# CompletePCBV3.net
KiCad netlist of a schematic drawn in EAGLE
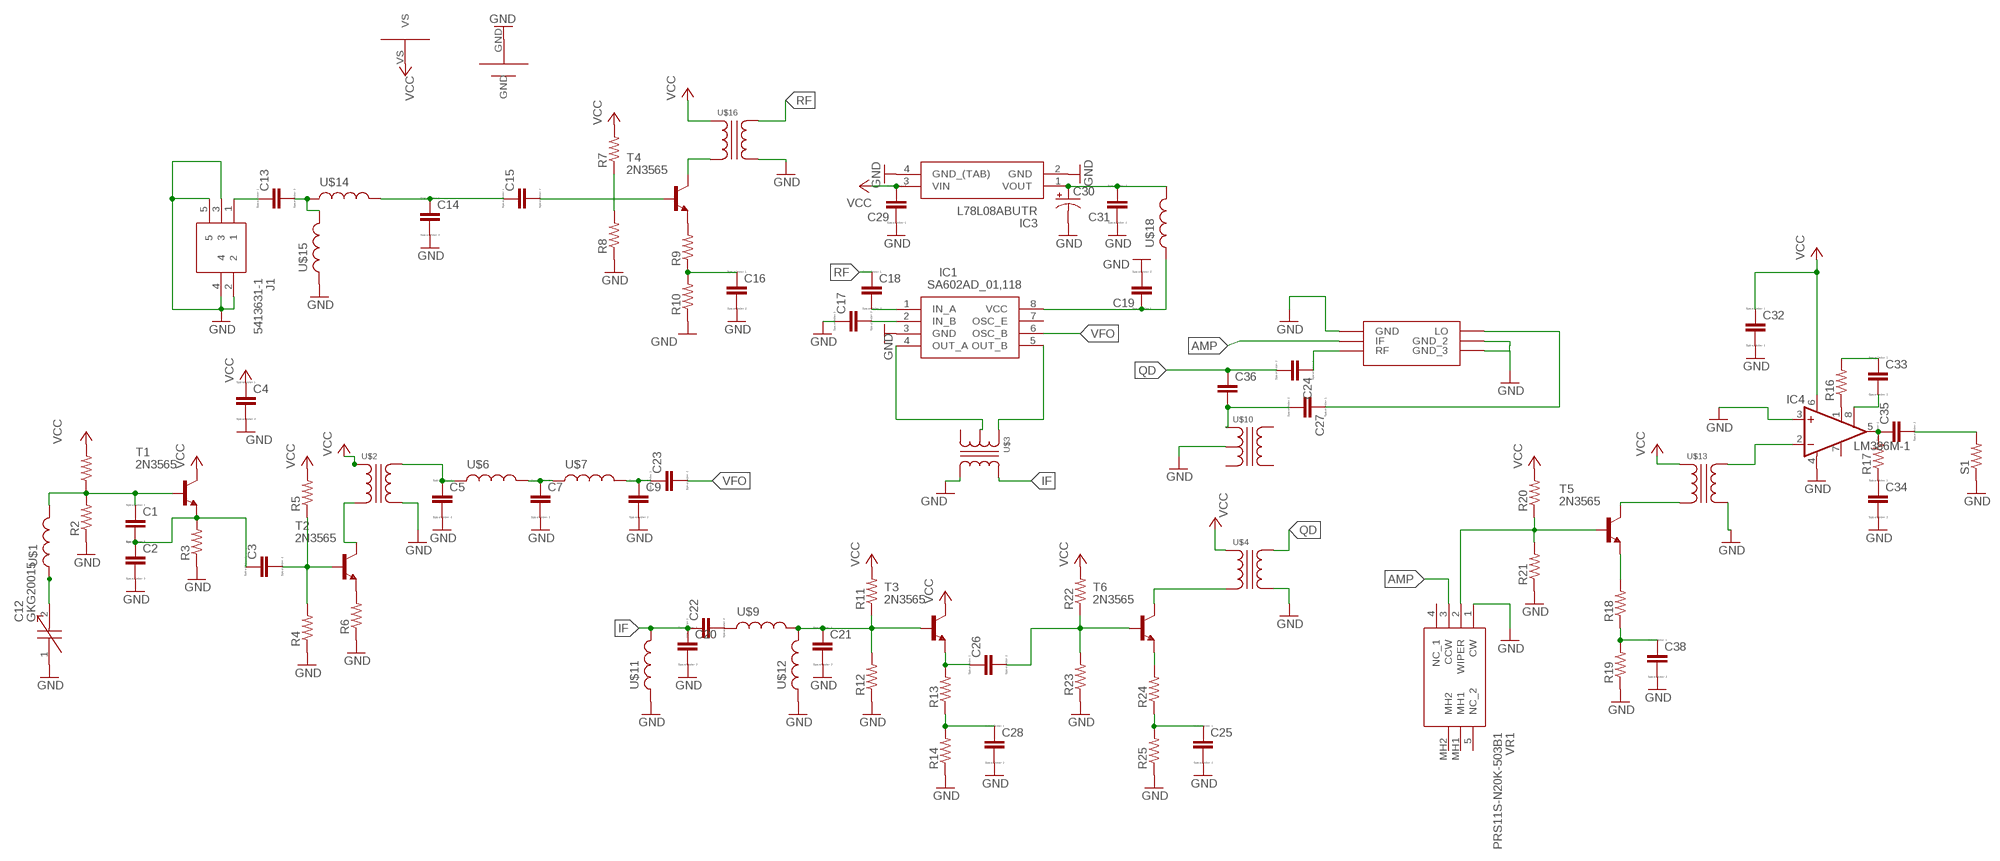
[diagram p0: schematic, sheet 1]

(export (version "E")
  (design (tool "Eeschema 10.0.6"))
  (components
    (comp (ref "C1") (value "C") (footprint "eagle-import:C0805") (libsource (lib "eagle-import") (part "C")))
    (comp (ref "C2") (value "C") (footprint "eagle-import:C0805") (libsource (lib "eagle-import") (part "C")))
    (comp (ref "C3") (value "C") (footprint "eagle-import:C0805") (libsource (lib "eagle-import") (part "C")))
    (comp (ref "C4") (value "C") (footprint "eagle-import:C0805") (libsource (lib "eagle-import") (part "C")))
    (comp (ref "C5") (value "C") (footprint "eagle-import:C0805") (libsource (lib "eagle-import") (part "C")))
    (comp (ref "C7") (value "C") (footprint "eagle-import:C0805") (libsource (lib "eagle-import") (part "C")))
    (comp (ref "C9") (value "C") (footprint "eagle-import:C0805") (libsource (lib "eagle-import") (part "C")))
    (comp (ref "C12")
      (value "GKG20015")
      (footprint "eagle-import:GKG20015")
      (fields (field (name "MOUSER_PART_NUMBER") "659-GKG20015"))
      (libsource (lib "eagle-import") (part "GKG20015"))
    )
    (comp (ref "C13")
      (value "C")
      (footprint "eagle-import:C0805")
      (libsource (lib "eagle-import") (part "C"))
    )
    (comp (ref "C14")
      (value "C")
      (footprint "eagle-import:C0805")
      (libsource (lib "eagle-import") (part "C"))
    )
    (comp (ref "C15")
      (value "C")
      (footprint "eagle-import:C0805")
      (libsource (lib "eagle-import") (part "C"))
    )
    (comp (ref "C16")
      (value "C")
      (footprint "eagle-import:C0805")
      (libsource (lib "eagle-import") (part "C"))
    )
    (comp (ref "C17")
      (value "C")
      (footprint "eagle-import:C0805")
      (libsource (lib "eagle-import") (part "C"))
    )
    (comp (ref "C18")
      (value "C")
      (footprint "eagle-import:C0805")
      (libsource (lib "eagle-import") (part "C"))
    )
    (comp (ref "C19")
      (value "C")
      (footprint "eagle-import:C0805")
      (libsource (lib "eagle-import") (part "C"))
    )
    (comp (ref "C20")
      (value "C")
      (footprint "eagle-import:C0805")
      (libsource (lib "eagle-import") (part "C"))
    )
    (comp (ref "C21")
      (value "C")
      (footprint "eagle-import:C0805")
      (libsource (lib "eagle-import") (part "C"))
    )
    (comp (ref "C22")
      (value "C")
      (footprint "eagle-import:C0805")
      (libsource (lib "eagle-import") (part "C"))
    )
    (comp (ref "C23")
      (value "C")
      (footprint "eagle-import:C0805")
      (libsource (lib "eagle-import") (part "C"))
    )
    (comp (ref "C24")
      (value "C")
      (footprint "eagle-import:C0805")
      (libsource (lib "eagle-import") (part "C"))
    )
    (comp (ref "C25")
      (value "C")
      (footprint "eagle-import:C0805")
      (libsource (lib "eagle-import") (part "C"))
    )
    (comp (ref "C26")
      (value "C")
      (footprint "eagle-import:C0805")
      (libsource (lib "eagle-import") (part "C"))
    )
    (comp (ref "C27")
      (value "C")
      (footprint "eagle-import:C0805")
      (libsource (lib "eagle-import") (part "C"))
    )
    (comp (ref "C28")
      (value "C")
      (footprint "eagle-import:C0805")
      (libsource (lib "eagle-import") (part "C"))
    )
    (comp (ref "C29")
      (value "C")
      (footprint "eagle-import:C0805")
      (libsource (lib "eagle-import") (part "C"))
    )
    (comp (ref "C30")
      (value "CPOL-US175TMP-0808")
      (footprint "eagle-import:175TMP-0808")
      (libsource (lib "eagle-import") (part "CPOL-US175TMP-0808"))
    )
    (comp (ref "C31")
      (value "C")
      (footprint "eagle-import:C0805")
      (libsource (lib "eagle-import") (part "C"))
    )
    (comp (ref "C32")
      (value "C")
      (footprint "eagle-import:C0805")
      (libsource (lib "eagle-import") (part "C"))
    )
    (comp (ref "C33")
      (value "C")
      (footprint "eagle-import:C0805")
      (libsource (lib "eagle-import") (part "C"))
    )
    (comp (ref "C34")
      (value "C")
      (footprint "eagle-import:C0805")
      (libsource (lib "eagle-import") (part "C"))
    )
    (comp (ref "C35")
      (value "C")
      (footprint "eagle-import:C0805")
      (libsource (lib "eagle-import") (part "C"))
    )
    (comp (ref "C36")
      (value "C-EUC0603")
      (footprint "eagle-import:C0603")
      (libsource (lib "eagle-import") (part "C-EUC0603"))
    )
    (comp (ref "C38")
      (value "C")
      (footprint "eagle-import:C0805")
      (libsource (lib "eagle-import") (part "C"))
    )
    (comp (ref "IC1")
      (value "SA602AD_01,118")
      (footprint "eagle-import:SOIC127P600X175-8N")
      (fields
        (field (name "MANUFACTURER_PART_NUMBER") "SA602AD/01,118")
        (field (name "MOUSER_PART_NUMBER") "771-SA602AD/01-T")
      )
      (libsource (lib "eagle-import") (part "SA602AD_01,118"))
    )
    (comp (ref "IC3")
      (value "L78L08ABUTR")
      (footprint "eagle-import:ST-SOT-89")
      (fields (field (name "MOUSER_PART_NUMBER") "511-L78L08ABU"))
      (libsource (lib "eagle-import") (part "L78L08ABUTR"))
    )
    (comp (ref "IC4")
      (value "LM386M-1")
      (footprint "eagle-import:SO08")
      (libsource (lib "eagle-import") (part "LM386?-M1"))
    )
    (comp (ref "J1")
      (value "5413631-1")
      (footprint "eagle-import:54136311")
      (fields (field (name "MOUSER_PART_NUMBER") "571-5413631-1"))
      (libsource (lib "eagle-import") (part "5413631-1"))
    )
    (comp (ref "R1")
      (value "R-US_R0805")
      (footprint "eagle-import:R0805")
      (libsource (lib "eagle-import") (part "resistor_348_R-US_R0805"))
    )
    (comp (ref "R2")
      (value "R-US_R0805")
      (footprint "eagle-import:R0805")
      (libsource (lib "eagle-import") (part "resistor_348_R-US_R0805"))
    )
    (comp (ref "R3")
      (value "R-US_R0805")
      (footprint "eagle-import:R0805")
      (libsource (lib "eagle-import") (part "resistor_348_R-US_R0805"))
    )
    (comp (ref "R4")
      (value "R-US_R0805")
      (footprint "eagle-import:R0805")
      (libsource (lib "eagle-import") (part "resistor_348_R-US_R0805"))
    )
    (comp (ref "R5")
      (value "R-US_R0805")
      (footprint "eagle-import:R0805")
      (libsource (lib "eagle-import") (part "resistor_348_R-US_R0805"))
    )
    (comp (ref "R6")
      (value "R-US_R0805")
      (footprint "eagle-import:R0805")
      (libsource (lib "eagle-import") (part "resistor_348_R-US_R0805"))
    )
    (comp (ref "R7")
      (value "R-US_R0805")
      (footprint "eagle-import:R0805")
      (libsource (lib "eagle-import") (part "resistor_348_R-US_R0805"))
    )
    (comp (ref "R8")
      (value "R-US_R0805")
      (footprint "eagle-import:R0805")
      (libsource (lib "eagle-import") (part "resistor_348_R-US_R0805"))
    )
    (comp (ref "R9")
      (value "R-US_R0805")
      (footprint "eagle-import:R0805")
      (libsource (lib "eagle-import") (part "resistor_348_R-US_R0805"))
    )
    (comp (ref "R10")
      (value "R-US_R0805")
      (footprint "eagle-import:R0805")
      (libsource (lib "eagle-import") (part "resistor_348_R-US_R0805"))
    )
    (comp (ref "R11")
      (value "R-US_R0805")
      (footprint "eagle-import:R0805")
      (libsource (lib "eagle-import") (part "resistor_348_R-US_R0805"))
    )
    (comp (ref "R12")
      (value "R-US_R0805")
      (footprint "eagle-import:R0805")
      (libsource (lib "eagle-import") (part "resistor_348_R-US_R0805"))
    )
    (comp (ref "R13")
      (value "R-US_R0805")
      (footprint "eagle-import:R0805")
      (libsource (lib "eagle-import") (part "resistor_348_R-US_R0805"))
    )
    (comp (ref "R14")
      (value "R-US_R0805")
      (footprint "eagle-import:R0805")
      (libsource (lib "eagle-import") (part "resistor_348_R-US_R0805"))
    )
    (comp (ref "R16")
      (value "R-US_R0805")
      (footprint "eagle-import:R0805")
      (libsource (lib "eagle-import") (part "resistor_348_R-US_R0805"))
    )
    (comp (ref "R17")
      (value "R-US_R0805")
      (footprint "eagle-import:R0805")
      (libsource (lib "eagle-import") (part "resistor_348_R-US_R0805"))
    )
    (comp (ref "R18")
      (value "R-US_R0805")
      (footprint "eagle-import:R0805")
      (libsource (lib "eagle-import") (part "resistor_348_R-US_R0805"))
    )
    (comp (ref "R19")
      (value "R-US_R0805")
      (footprint "eagle-import:R0805")
      (libsource (lib "eagle-import") (part "resistor_348_R-US_R0805"))
    )
    (comp (ref "R20")
      (value "R-US_R0805")
      (footprint "eagle-import:R0805")
      (libsource (lib "eagle-import") (part "resistor_348_R-US_R0805"))
    )
    (comp (ref "R21")
      (value "R-US_R0805")
      (footprint "eagle-import:R0805")
      (libsource (lib "eagle-import") (part "resistor_348_R-US_R0805"))
    )
    (comp (ref "R22")
      (value "R-US_R0805")
      (footprint "eagle-import:R0805")
      (libsource (lib "eagle-import") (part "resistor_348_R-US_R0805"))
    )
    (comp (ref "R23")
      (value "R-US_R0805")
      (footprint "eagle-import:R0805")
      (libsource (lib "eagle-import") (part "resistor_348_R-US_R0805"))
    )
    (comp (ref "R24")
      (value "R-US_R0805")
      (footprint "eagle-import:R0805")
      (libsource (lib "eagle-import") (part "resistor_348_R-US_R0805"))
    )
    (comp (ref "R25")
      (value "R-US_R0805")
      (footprint "eagle-import:R0805")
      (libsource (lib "eagle-import") (part "resistor_348_R-US_R0805"))
    )
    (comp (ref "S1")
      (value "R-US_0207/5V")
      (footprint "eagle-import:0207_5V")
      (libsource (lib "eagle-import") (part "R-US_0207/5V"))
    )
    (comp (ref "T1")
      (value "2N3565")
      (footprint "eagle-import:TO92")
      (libsource (lib "eagle-import") (part "2N3565"))
    )
    (comp (ref "T2")
      (value "2N3565")
      (footprint "eagle-import:TO92")
      (libsource (lib "eagle-import") (part "2N3565"))
    )
    (comp (ref "T3")
      (value "2N3565")
      (footprint "eagle-import:TO92")
      (libsource (lib "eagle-import") (part "2N3565"))
    )
    (comp (ref "T4")
      (value "2N3565")
      (footprint "eagle-import:TO92")
      (libsource (lib "eagle-import") (part "2N3565"))
    )
    (comp (ref "T5")
      (value "2N3565")
      (footprint "eagle-import:TO92")
      (libsource (lib "eagle-import") (part "2N3565"))
    )
    (comp (ref "T6")
      (value "2N3565")
      (footprint "eagle-import:TO92")
      (libsource (lib "eagle-import") (part "2N3565"))
    )
    (comp (ref "U$1")
      (value "WOUNDINDUCTOR")
      (footprint "eagle-import:WOUNDINDUCTOR")
      (libsource (lib "eagle-import") (part "WOUNDINDUCTOR"))
    )
    (comp (ref "U$2")
      (value "RFTRANSFORMER")
      (footprint "eagle-import:RFTRABSFORMER")
      (libsource (lib "eagle-import") (part "RFTRANSFORMER"))
    )
    (comp (ref "U$3")
      (value "42IF123")
      (footprint "eagle-import:42IF123")
      (libsource (lib "eagle-import") (part "42IF123"))
    )
    (comp (ref "U$4")
      (value "RFTRANSFORMER")
      (footprint "eagle-import:RFTRABSFORMER")
      (libsource (lib "eagle-import") (part "RFTRANSFORMER"))
    )
    (comp (ref "U$5")
      (value "ALLIGATORCLIPS")
      (footprint "eagle-import:ALLIGATORCONNECTOR")
      (libsource (lib "eagle-import") (part "ALLIGATORCLIPS"))
    )
    (comp (ref "U$6")
      (value "WOUNDINDUCTOR")
      (footprint "eagle-import:WOUNDINDUCTOR")
      (libsource (lib "eagle-import") (part "WOUNDINDUCTOR"))
    )
    (comp (ref "U$7")
      (value "WOUNDINDUCTOR")
      (footprint "eagle-import:WOUNDINDUCTOR")
      (libsource (lib "eagle-import") (part "WOUNDINDUCTOR"))
    )
    (comp (ref "U$9")
      (value "WOUNDINDUCTOR")
      (footprint "eagle-import:WOUNDINDUCTOR")
      (libsource (lib "eagle-import") (part "WOUNDINDUCTOR"))
    )
    (comp (ref "U$10")
      (value "42IF123")
      (footprint "eagle-import:42IF123")
      (libsource (lib "eagle-import") (part "42IF123"))
    )
    (comp (ref "U$11")
      (value "WOUNDINDUCTOR")
      (footprint "eagle-import:WOUNDINDUCTOR")
      (libsource (lib "eagle-import") (part "WOUNDINDUCTOR"))
    )
    (comp (ref "U$12")
      (value "WOUNDINDUCTOR")
      (footprint "eagle-import:WOUNDINDUCTOR")
      (libsource (lib "eagle-import") (part "WOUNDINDUCTOR"))
    )
    (comp (ref "U$13")
      (value "RFTRANSFORMER")
      (footprint "eagle-import:RFTRABSFORMER")
      (libsource (lib "eagle-import") (part "RFTRANSFORMER"))
    )
    (comp (ref "U$14")
      (value "WOUNDINDUCTOR")
      (footprint "eagle-import:WOUNDINDUCTOR")
      (libsource (lib "eagle-import") (part "WOUNDINDUCTOR"))
    )
    (comp (ref "U$15")
      (value "WOUNDINDUCTOR")
      (footprint "eagle-import:WOUNDINDUCTOR")
      (libsource (lib "eagle-import") (part "WOUNDINDUCTOR"))
    )
    (comp (ref "U$16")
      (value "RFTRANSFORMER")
      (footprint "eagle-import:RFTRABSFORMER")
      (libsource (lib "eagle-import") (part "RFTRANSFORMER"))
    )
    (comp (ref "U$17")
      (value "ADE-1")
      (footprint "eagle-import:ADE-1")
      (libsource (lib "eagle-import") (part "ADE-1"))
    )
    (comp (ref "U$18")
      (value "WOUNDINDUCTOR")
      (footprint "eagle-import:WOUNDINDUCTOR")
      (libsource (lib "eagle-import") (part "WOUNDINDUCTOR"))
    )
    (comp (ref "VR1")
      (value "PRS11S-N20K-503B1")
      (footprint "eagle-import:PRS11SN20K503B1")
      (fields (field (name "MOUSER_PART_NUMBER") "652-PRS11SN20K503B1"))
      (libsource (lib "eagle-import") (part "PRS11S-N20K-503B1"))
    )
  )
  (nets
    (net (code "1") (name "AMP") (class "Default")
      (node (ref "U$17") (pin "IF") (pinfunction "IF_IF") (pintype "bidirectional"))
      (node (ref "VR1") (pin "3") (pinfunction "CCW_3") (pintype "bidirectional"))
    )
    (net (code "2") (name "GND") (class "Default")
      (node (ref "C12") (pin "1") (pinfunction "1_1") (pintype "bidirectional"))
      (node (ref "C14") (pin "2") (pinfunction "2_2") (pintype "passive"))
      (node (ref "C16") (pin "2") (pinfunction "2_2") (pintype "passive"))
      (node (ref "C17") (pin "1") (pinfunction "1_1") (pintype "passive"))
      (node (ref "C19") (pin "2") (pinfunction "2_2") (pintype "passive"))
      (node (ref "C2") (pin "2") (pinfunction "2_2") (pintype "passive"))
      (node (ref "C20") (pin "2") (pinfunction "2_2") (pintype "passive"))
      (node (ref "C21") (pin "2") (pinfunction "2_2") (pintype "passive"))
      (node (ref "C25") (pin "2") (pinfunction "2_2") (pintype "passive"))
      (node (ref "C28") (pin "2") (pinfunction "2_2") (pintype "passive"))
      (node (ref "C29") (pin "1") (pinfunction "1_1") (pintype "passive"))
      (node (ref "C30") (pin "-") (pinfunction "-_-") (pintype "passive"))
      (node (ref "C31") (pin "1") (pinfunction "1_1") (pintype "passive"))
      (node (ref "C32") (pin "2") (pinfunction "2_2") (pintype "passive"))
      (node (ref "C34") (pin "2") (pinfunction "2_2") (pintype "passive"))
      (node (ref "C38") (pin "2") (pinfunction "2_2") (pintype "passive"))
      (node (ref "C4") (pin "2") (pinfunction "2_2") (pintype "passive"))
      (node (ref "C5") (pin "2") (pinfunction "2_2") (pintype "passive"))
      (node (ref "C7") (pin "2") (pinfunction "2_2") (pintype "passive"))
      (node (ref "C9") (pin "2") (pinfunction "2_2") (pintype "passive"))
      (node (ref "IC1") (pin "3") (pinfunction "GND_3") (pintype "power_in"))
      (node (ref "IC3") (pin "2") (pinfunction "GND_2") (pintype "power_in"))
      (node (ref "IC3") (pin "4") (pinfunction "GND_(TAB)_4") (pintype "power_in"))
      (node (ref "IC4") (pin "3") (pinfunction "+IN_3") (pintype "input"))
      (node (ref "IC4") (pin "4") (pinfunction "GND_4") (pintype "power_in"))
      (node (ref "J1") (pin "2") (pinfunction "2_2") (pintype "bidirectional"))
      (node (ref "J1") (pin "3") (pinfunction "3_3") (pintype "bidirectional"))
      (node (ref "J1") (pin "4") (pinfunction "4_4") (pintype "bidirectional"))
      (node (ref "J1") (pin "5") (pinfunction "5_5") (pintype "bidirectional"))
      (node (ref "R10") (pin "1") (pinfunction "1_1") (pintype "passive"))
      (node (ref "R12") (pin "1") (pinfunction "1_1") (pintype "passive"))
      (node (ref "R14") (pin "1") (pinfunction "1_1") (pintype "passive"))
      (node (ref "R19") (pin "1") (pinfunction "1_1") (pintype "passive"))
      (node (ref "R2") (pin "1") (pinfunction "1_1") (pintype "passive"))
      (node (ref "R21") (pin "1") (pinfunction "1_1") (pintype "passive"))
      (node (ref "R23") (pin "1") (pinfunction "1_1") (pintype "passive"))
      (node (ref "R25") (pin "1") (pinfunction "1_1") (pintype "passive"))
      (node (ref "R3") (pin "1") (pinfunction "1_1") (pintype "passive"))
      (node (ref "R4") (pin "1") (pinfunction "1_1") (pintype "passive"))
      (node (ref "R6") (pin "1") (pinfunction "1_1") (pintype "passive"))
      (node (ref "R8") (pin "1") (pinfunction "1_1") (pintype "passive"))
      (node (ref "S1") (pin "1") (pinfunction "1_1") (pintype "passive"))
      (node (ref "U$10") (pin "P$1") (pinfunction "P$5_P$1") (pintype "bidirectional"))
      (node (ref "U$11") (pin "1") (pinfunction "1_1") (pintype "bidirectional"))
      (node (ref "U$12") (pin "1") (pinfunction "1_1") (pintype "bidirectional"))
      (node (ref "U$13") (pin "P$4") (pinfunction "P$3_P$4") (pintype "bidirectional"))
      (node (ref "U$15") (pin "1") (pinfunction "1_1") (pintype "bidirectional"))
      (node (ref "U$16") (pin "P$4") (pinfunction "P$3_P$4") (pintype "bidirectional"))
      (node (ref "U$17") (pin "GND") (pinfunction "GND_GND") (pintype "bidirectional"))
      (node (ref "U$17") (pin "GND2") (pinfunction "GND_2_GND2") (pintype "bidirectional"))
      (node (ref "U$17") (pin "GND3") (pinfunction "GND_3_GND3") (pintype "bidirectional"))
      (node (ref "U$2") (pin "P$4") (pinfunction "P$3_P$4") (pintype "bidirectional"))
      (node (ref "U$3") (pin "P$4") (pinfunction "P$3_P$4") (pintype "bidirectional"))
      (node (ref "U$4") (pin "P$4") (pinfunction "P$3_P$4") (pintype "bidirectional"))
      (node (ref "U$5") (pin "GND") (pinfunction "GND_GND") (pintype "bidirectional"))
      (node (ref "VR1") (pin "1") (pinfunction "CW_1") (pintype "bidirectional"))
    )
    (net (code "3") (name "IF") (class "Default")
      (node (ref "C20") (pin "1") (pinfunction "1_1") (pintype "passive"))
      (node (ref "C22") (pin "1") (pinfunction "1_1") (pintype "passive"))
      (node (ref "U$11") (pin "2") (pinfunction "2_2") (pintype "bidirectional"))
      (node (ref "U$3") (pin "P$5") (pinfunction "P$4_P$5") (pintype "bidirectional"))
    )
    (net (code "4") (name "Net-(C7-Pad1)") (class "Default")
      (node (ref "C7") (pin "1") (pinfunction "1_1") (pintype "passive"))
      (node (ref "U$6") (pin "2") (pinfunction "2_2") (pintype "bidirectional"))
      (node (ref "U$7") (pin "1") (pinfunction "1_1") (pintype "bidirectional"))
    )
    (net (code "5") (name "Net-(C12-Pad2)") (class "Default")
      (node (ref "C12") (pin "2") (pinfunction "2_2") (pintype "bidirectional"))
      (node (ref "U$1") (pin "1") (pinfunction "1_1") (pintype "bidirectional"))
    )
    (net (code "6") (name "Net-(C13-Pad1)") (class "Default")
      (node (ref "C13") (pin "1") (pinfunction "1_1") (pintype "passive"))
      (node (ref "J1") (pin "1") (pinfunction "1_1") (pintype "bidirectional"))
    )
    (net (code "7") (name "Net-(C13-Pad2)") (class "Default")
      (node (ref "C13") (pin "2") (pinfunction "2_2") (pintype "passive"))
      (node (ref "U$14") (pin "1") (pinfunction "1_1") (pintype "bidirectional"))
      (node (ref "U$15") (pin "2") (pinfunction "2_2") (pintype "bidirectional"))
    )
    (net (code "8") (name "Net-(C14-Pad1)") (class "Default")
      (node (ref "C14") (pin "1") (pinfunction "1_1") (pintype "passive"))
      (node (ref "C15") (pin "1") (pinfunction "1_1") (pintype "passive"))
      (node (ref "U$14") (pin "2") (pinfunction "2_2") (pintype "bidirectional"))
    )
    (net (code "9") (name "Net-(C16-Pad1)") (class "Default")
      (node (ref "C16") (pin "1") (pinfunction "1_1") (pintype "passive"))
      (node (ref "R10") (pin "2") (pinfunction "2_2") (pintype "passive"))
      (node (ref "R9") (pin "1") (pinfunction "1_1") (pintype "passive"))
    )
    (net (code "10") (name "Net-(C22-Pad2)") (class "Default")
      (node (ref "C22") (pin "2") (pinfunction "2_2") (pintype "passive"))
      (node (ref "U$9") (pin "1") (pinfunction "1_1") (pintype "bidirectional"))
    )
    (net (code "11") (name "Net-(C23-Pad1)") (class "Default")
      (node (ref "C23") (pin "1") (pinfunction "1_1") (pintype "passive"))
      (node (ref "C9") (pin "1") (pinfunction "1_1") (pintype "passive"))
      (node (ref "U$7") (pin "2") (pinfunction "2_2") (pintype "bidirectional"))
    )
    (net (code "12") (name "Net-(C24-Pad1)") (class "Default")
      (node (ref "C24") (pin "1") (pinfunction "1_1") (pintype "passive"))
      (node (ref "U$17") (pin "RF") (pinfunction "RF_RF") (pintype "bidirectional"))
    )
    (net (code "13") (name "Net-(C25-Pad1)") (class "Default")
      (node (ref "C25") (pin "1") (pinfunction "1_1") (pintype "passive"))
      (node (ref "R24") (pin "1") (pinfunction "1_1") (pintype "passive"))
      (node (ref "R25") (pin "2") (pinfunction "2_2") (pintype "passive"))
    )
    (net (code "14") (name "Net-(C27-Pad1)") (class "Default")
      (node (ref "C27") (pin "1") (pinfunction "1_1") (pintype "passive"))
      (node (ref "U$17") (pin "LO") (pinfunction "LO_LO") (pintype "bidirectional"))
    )
    (net (code "15") (name "Net-(C28-Pad1)") (class "Default")
      (node (ref "C28") (pin "1") (pinfunction "1_1") (pintype "passive"))
      (node (ref "R13") (pin "1") (pinfunction "1_1") (pintype "passive"))
      (node (ref "R14") (pin "2") (pinfunction "2_2") (pintype "passive"))
    )
    (net (code "16") (name "Net-(C33-Pad1)") (class "Default")
      (node (ref "C33") (pin "1") (pinfunction "1_1") (pintype "passive"))
      (node (ref "R16") (pin "2") (pinfunction "2_2") (pintype "passive"))
    )
    (net (code "17") (name "Net-(C33-Pad2)") (class "Default")
      (node (ref "C33") (pin "2") (pinfunction "2_2") (pintype "passive"))
      (node (ref "IC4") (pin "8") (pinfunction "GAIN_8") (pintype "passive"))
    )
    (net (code "18") (name "Net-(C34-Pad1)") (class "Default")
      (node (ref "C34") (pin "1") (pinfunction "1_1") (pintype "passive"))
      (node (ref "R17") (pin "1") (pinfunction "1_1") (pintype "passive"))
    )
    (net (code "19") (name "Net-(C35-Pad2)") (class "Default")
      (node (ref "C35") (pin "2") (pinfunction "2_2") (pintype "passive"))
      (node (ref "S1") (pin "2") (pinfunction "2_2") (pintype "passive"))
    )
    (net (code "20") (name "Net-(C38-Pad1)") (class "Default")
      (node (ref "C38") (pin "1") (pinfunction "1_1") (pintype "passive"))
      (node (ref "R18") (pin "1") (pinfunction "1_1") (pintype "passive"))
      (node (ref "R19") (pin "2") (pinfunction "2_2") (pintype "passive"))
    )
    (net (code "21") (name "Net-(IC1-IN_A)") (class "Default")
      (node (ref "C18") (pin "2") (pinfunction "2_2") (pintype "passive"))
      (node (ref "IC1") (pin "1") (pinfunction "IN_A_1") (pintype "input"))
    )
    (net (code "22") (name "Net-(IC1-IN_B)") (class "Default")
      (node (ref "C17") (pin "2") (pinfunction "2_2") (pintype "passive"))
      (node (ref "IC1") (pin "2") (pinfunction "IN_B_2") (pintype "input"))
    )
    (net (code "23") (name "Net-(IC1-OUT_A)") (class "Default")
      (node (ref "IC1") (pin "4") (pinfunction "OUT_A_4") (pintype "output"))
      (node (ref "U$3") (pin "P$1") (pinfunction "P$5_P$1") (pintype "bidirectional"))
    )
    (net (code "24") (name "Net-(IC1-OUT_B)") (class "Default")
      (node (ref "IC1") (pin "5") (pinfunction "OUT_B_5") (pintype "output"))
      (node (ref "U$3") (pin "P$2") (pinfunction "P$1_P$2") (pintype "bidirectional"))
    )
    (net (code "25") (name "Net-(IC1-VCC)") (class "Default")
      (node (ref "C19") (pin "1") (pinfunction "1_1") (pintype "passive"))
      (node (ref "IC1") (pin "8") (pinfunction "VCC_8") (pintype "power_in"))
      (node (ref "U$18") (pin "1") (pinfunction "1_1") (pintype "bidirectional"))
    )
    (net (code "26") (name "Net-(IC3-VOUT)") (class "Default")
      (node (ref "C30") (pin "+") (pinfunction "+_+") (pintype "passive"))
      (node (ref "C31") (pin "2") (pinfunction "2_2") (pintype "passive"))
      (node (ref "IC3") (pin "1") (pinfunction "VOUT_1") (pintype "output"))
      (node (ref "U$18") (pin "2") (pinfunction "2_2") (pintype "bidirectional"))
    )
    (net (code "27") (name "Net-(IC4--IN)") (class "Default")
      (node (ref "IC4") (pin "2") (pinfunction "-IN_2") (pintype "input"))
      (node (ref "U$13") (pin "P$3") (pinfunction "P$4_P$3") (pintype "bidirectional"))
    )
    (net (code "28") (name "Net-(IC4-GAIN-Pad1)") (class "Default")
      (node (ref "IC4") (pin "1") (pinfunction "GAIN_1") (pintype "passive"))
      (node (ref "R16") (pin "1") (pinfunction "1_1") (pintype "passive"))
    )
    (net (code "29") (name "Net-(IC4-OUT)") (class "Default")
      (node (ref "C35") (pin "1") (pinfunction "1_1") (pintype "passive"))
      (node (ref "IC4") (pin "5") (pinfunction "OUT_5") (pintype "output"))
      (node (ref "R17") (pin "2") (pinfunction "2_2") (pintype "passive"))
    )
    (net (code "30") (name "Net-(R7-Pad1)") (class "Default")
      (node (ref "R7") (pin "1") (pinfunction "1_1") (pintype "passive"))
      (node (ref "R8") (pin "2") (pinfunction "2_2") (pintype "passive"))
    )
    (net (code "31") (name "Net-(T1-B)") (class "Default")
      (node (ref "C1") (pin "1") (pinfunction "1_1") (pintype "passive"))
      (node (ref "R1") (pin "1") (pinfunction "1_1") (pintype "passive"))
      (node (ref "R2") (pin "2") (pinfunction "2_2") (pintype "passive"))
      (node (ref "T1") (pin "2") (pinfunction "B_2") (pintype "passive"))
      (node (ref "U$1") (pin "2") (pinfunction "2_2") (pintype "bidirectional"))
    )
    (net (code "32") (name "Net-(T1-E)") (class "Default")
      (node (ref "C1") (pin "2") (pinfunction "2_2") (pintype "passive"))
      (node (ref "C2") (pin "1") (pinfunction "1_1") (pintype "passive"))
      (node (ref "C3") (pin "1") (pinfunction "1_1") (pintype "passive"))
      (node (ref "R3") (pin "2") (pinfunction "2_2") (pintype "passive"))
      (node (ref "T1") (pin "3") (pinfunction "E_3") (pintype "passive"))
    )
    (net (code "33") (name "Net-(T2-B)") (class "Default")
      (node (ref "C3") (pin "2") (pinfunction "2_2") (pintype "passive"))
      (node (ref "R4") (pin "2") (pinfunction "2_2") (pintype "passive"))
      (node (ref "R5") (pin "1") (pinfunction "1_1") (pintype "passive"))
      (node (ref "T2") (pin "2") (pinfunction "B_2") (pintype "passive"))
    )
    (net (code "34") (name "Net-(T2-C)") (class "Default")
      (node (ref "T2") (pin "1") (pinfunction "C_1") (pintype "passive"))
      (node (ref "U$2") (pin "P$2") (pinfunction "P$2_P$2") (pintype "bidirectional"))
    )
    (net (code "35") (name "Net-(T2-E)") (class "Default")
      (node (ref "R6") (pin "2") (pinfunction "2_2") (pintype "passive"))
      (node (ref "T2") (pin "3") (pinfunction "E_3") (pintype "passive"))
    )
    (net (code "36") (name "Net-(T3-B)") (class "Default")
      (node (ref "C21") (pin "1") (pinfunction "1_1") (pintype "passive"))
      (node (ref "R11") (pin "1") (pinfunction "1_1") (pintype "passive"))
      (node (ref "R12") (pin "2") (pinfunction "2_2") (pintype "passive"))
      (node (ref "T3") (pin "2") (pinfunction "B_2") (pintype "passive"))
      (node (ref "U$12") (pin "2") (pinfunction "2_2") (pintype "bidirectional"))
      (node (ref "U$9") (pin "2") (pinfunction "2_2") (pintype "bidirectional"))
    )
    (net (code "37") (name "Net-(T3-E)") (class "Default")
      (node (ref "C26") (pin "1") (pinfunction "1_1") (pintype "passive"))
      (node (ref "R13") (pin "2") (pinfunction "2_2") (pintype "passive"))
      (node (ref "T3") (pin "3") (pinfunction "E_3") (pintype "passive"))
    )
    (net (code "38") (name "Net-(T4-B)") (class "Default")
      (node (ref "C15") (pin "2") (pinfunction "2_2") (pintype "passive"))
      (node (ref "T4") (pin "2") (pinfunction "B_2") (pintype "passive"))
    )
    (net (code "39") (name "Net-(T4-C)") (class "Default")
      (node (ref "T4") (pin "1") (pinfunction "C_1") (pintype "passive"))
      (node (ref "U$16") (pin "P$2") (pinfunction "P$2_P$2") (pintype "bidirectional"))
    )
    (net (code "40") (name "Net-(T4-E)") (class "Default")
      (node (ref "R9") (pin "2") (pinfunction "2_2") (pintype "passive"))
      (node (ref "T4") (pin "3") (pinfunction "E_3") (pintype "passive"))
    )
    (net (code "41") (name "Net-(T5-B)") (class "Default")
      (node (ref "R20") (pin "1") (pinfunction "1_1") (pintype "passive"))
      (node (ref "R21") (pin "2") (pinfunction "2_2") (pintype "passive"))
      (node (ref "T5") (pin "2") (pinfunction "B_2") (pintype "passive"))
      (node (ref "VR1") (pin "2") (pinfunction "WIPER_2") (pintype "bidirectional"))
    )
    (net (code "42") (name "Net-(T5-C)") (class "Default")
      (node (ref "T5") (pin "1") (pinfunction "C_1") (pintype "passive"))
      (node (ref "U$13") (pin "P$2") (pinfunction "P$2_P$2") (pintype "bidirectional"))
    )
    (net (code "43") (name "Net-(T5-E)") (class "Default")
      (node (ref "R18") (pin "2") (pinfunction "2_2") (pintype "passive"))
      (node (ref "T5") (pin "3") (pinfunction "E_3") (pintype "passive"))
    )
    (net (code "44") (name "Net-(T6-B)") (class "Default")
      (node (ref "C26") (pin "2") (pinfunction "2_2") (pintype "passive"))
      (node (ref "R22") (pin "1") (pinfunction "1_1") (pintype "passive"))
      (node (ref "R23") (pin "2") (pinfunction "2_2") (pintype "passive"))
      (node (ref "T6") (pin "2") (pinfunction "B_2") (pintype "passive"))
    )
    (net (code "45") (name "Net-(T6-C)") (class "Default")
      (node (ref "T6") (pin "1") (pinfunction "C_1") (pintype "passive"))
      (node (ref "U$4") (pin "P$2") (pinfunction "P$2_P$2") (pintype "bidirectional"))
    )
    (net (code "46") (name "Net-(T6-E)") (class "Default")
      (node (ref "R24") (pin "2") (pinfunction "2_2") (pintype "passive"))
      (node (ref "T6") (pin "3") (pinfunction "E_3") (pintype "passive"))
    )
    (net (code "47") (name "Net-(U$2-P$4)") (class "Default")
      (node (ref "C5") (pin "1") (pinfunction "1_1") (pintype "passive"))
      (node (ref "U$2") (pin "P$3") (pinfunction "P$4_P$3") (pintype "bidirectional"))
      (node (ref "U$6") (pin "1") (pinfunction "1_1") (pintype "bidirectional"))
    )
    (net (code "48") (name "Net-(U$10-P$1)") (class "Default")
      (node (ref "C27") (pin "2") (pinfunction "2_2") (pintype "passive"))
      (node (ref "C36") (pin "2") (pinfunction "2_2") (pintype "passive"))
      (node (ref "U$10") (pin "P$2") (pinfunction "P$1_P$2") (pintype "bidirectional"))
    )
    (net (code "49") (name "QD") (class "Default")
      (node (ref "C24") (pin "2") (pinfunction "2_2") (pintype "passive"))
      (node (ref "C36") (pin "1") (pinfunction "1_1") (pintype "passive"))
      (node (ref "U$4") (pin "P$3") (pinfunction "P$4_P$3") (pintype "bidirectional"))
    )
    (net (code "50") (name "RF") (class "Default")
      (node (ref "C18") (pin "1") (pinfunction "1_1") (pintype "passive"))
      (node (ref "U$16") (pin "P$3") (pinfunction "P$4_P$3") (pintype "bidirectional"))
    )
    (net (code "51") (name "VCC") (class "Default")
      (node (ref "C29") (pin "2") (pinfunction "2_2") (pintype "passive"))
      (node (ref "C32") (pin "1") (pinfunction "1_1") (pintype "passive"))
      (node (ref "C4") (pin "1") (pinfunction "1_1") (pintype "passive"))
      (node (ref "IC3") (pin "3") (pinfunction "VIN_3") (pintype "input"))
      (node (ref "IC4") (pin "6") (pinfunction "VS_6") (pintype "power_in"))
      (node (ref "R1") (pin "2") (pinfunction "2_2") (pintype "passive"))
      (node (ref "R11") (pin "2") (pinfunction "2_2") (pintype "passive"))
      (node (ref "R20") (pin "2") (pinfunction "2_2") (pintype "passive"))
      (node (ref "R22") (pin "2") (pinfunction "2_2") (pintype "passive"))
      (node (ref "R5") (pin "2") (pinfunction "2_2") (pintype "passive"))
      (node (ref "R7") (pin "2") (pinfunction "2_2") (pintype "passive"))
      (node (ref "T1") (pin "1") (pinfunction "C_1") (pintype "passive"))
      (node (ref "T3") (pin "1") (pinfunction "C_1") (pintype "passive"))
      (node (ref "U$13") (pin "P$1") (pinfunction "P$1_P$1") (pintype "bidirectional"))
      (node (ref "U$16") (pin "P$1") (pinfunction "P$1_P$1") (pintype "bidirectional"))
      (node (ref "U$2") (pin "P$1") (pinfunction "P$1_P$1") (pintype "bidirectional"))
      (node (ref "U$4") (pin "P$1") (pinfunction "P$1_P$1") (pintype "bidirectional"))
      (node (ref "U$5") (pin "VS") (pinfunction "VS_VS") (pintype "bidirectional"))
    )
    (net (code "52") (name "VFO") (class "Default")
      (node (ref "C23") (pin "2") (pinfunction "2_2") (pintype "passive"))
      (node (ref "IC1") (pin "6") (pinfunction "OSC_B_6") (pintype "bidirectional"))
    )
    (net (code "53") (name "unconnected-(IC1-OSC_E-Pad7)") (class "Default")
      (node (ref "IC1") (pin "7") (pinfunction "OSC_E_7") (pintype "bidirectional"))
    )
    (net (code "54") (name "unconnected-(IC4-BYPASS-Pad7)") (class "Default")
      (node (ref "IC4") (pin "7") (pinfunction "BYPASS_7") (pintype "passive"))
    )
    (net (code "55") (name "unconnected-(U$3-P$2-PadP$3)") (class "Default")
      (node (ref "U$3") (pin "P$3") (pinfunction "P$2_P$3") (pintype "bidirectional"))
    )
    (net (code "56") (name "unconnected-(U$10-P$2-PadP$3)") (class "Default")
      (node (ref "U$10") (pin "P$3") (pinfunction "P$2_P$3") (pintype "bidirectional"))
    )
    (net (code "57") (name "unconnected-(U$10-P$3-PadP$4)") (class "Default")
      (node (ref "U$10") (pin "P$4") (pinfunction "P$3_P$4") (pintype "bidirectional"))
    )
    (net (code "58") (name "unconnected-(U$10-P$4-PadP$5)") (class "Default")
      (node (ref "U$10") (pin "P$5") (pinfunction "P$4_P$5") (pintype "bidirectional"))
    )
    (net (code "59") (name "unconnected-(VR1-NC_1-Pad4)") (class "Default")
      (node (ref "VR1") (pin "4") (pinfunction "NC_1_4") (pintype "bidirectional"))
    )
    (net (code "60") (name "unconnected-(VR1-NC_2-Pad5)") (class "Default")
      (node (ref "VR1") (pin "5") (pinfunction "NC_2_5") (pintype "bidirectional"))
    )
    (net (code "61") (name "unconnected-(VR1-PadMH1)") (class "Default")
      (node (ref "VR1") (pin "MH1") (pinfunction "MH1_MH1") (pintype "bidirectional"))
    )
    (net (code "62") (name "unconnected-(VR1-PadMH2)") (class "Default")
      (node (ref "VR1") (pin "MH2") (pinfunction "MH2_MH2") (pintype "bidirectional"))
    )
  )
)
